# SAMD20_Xplained_Pro_Target_MCU.net
KiCad netlist of a schematic drawn in Altium Designer
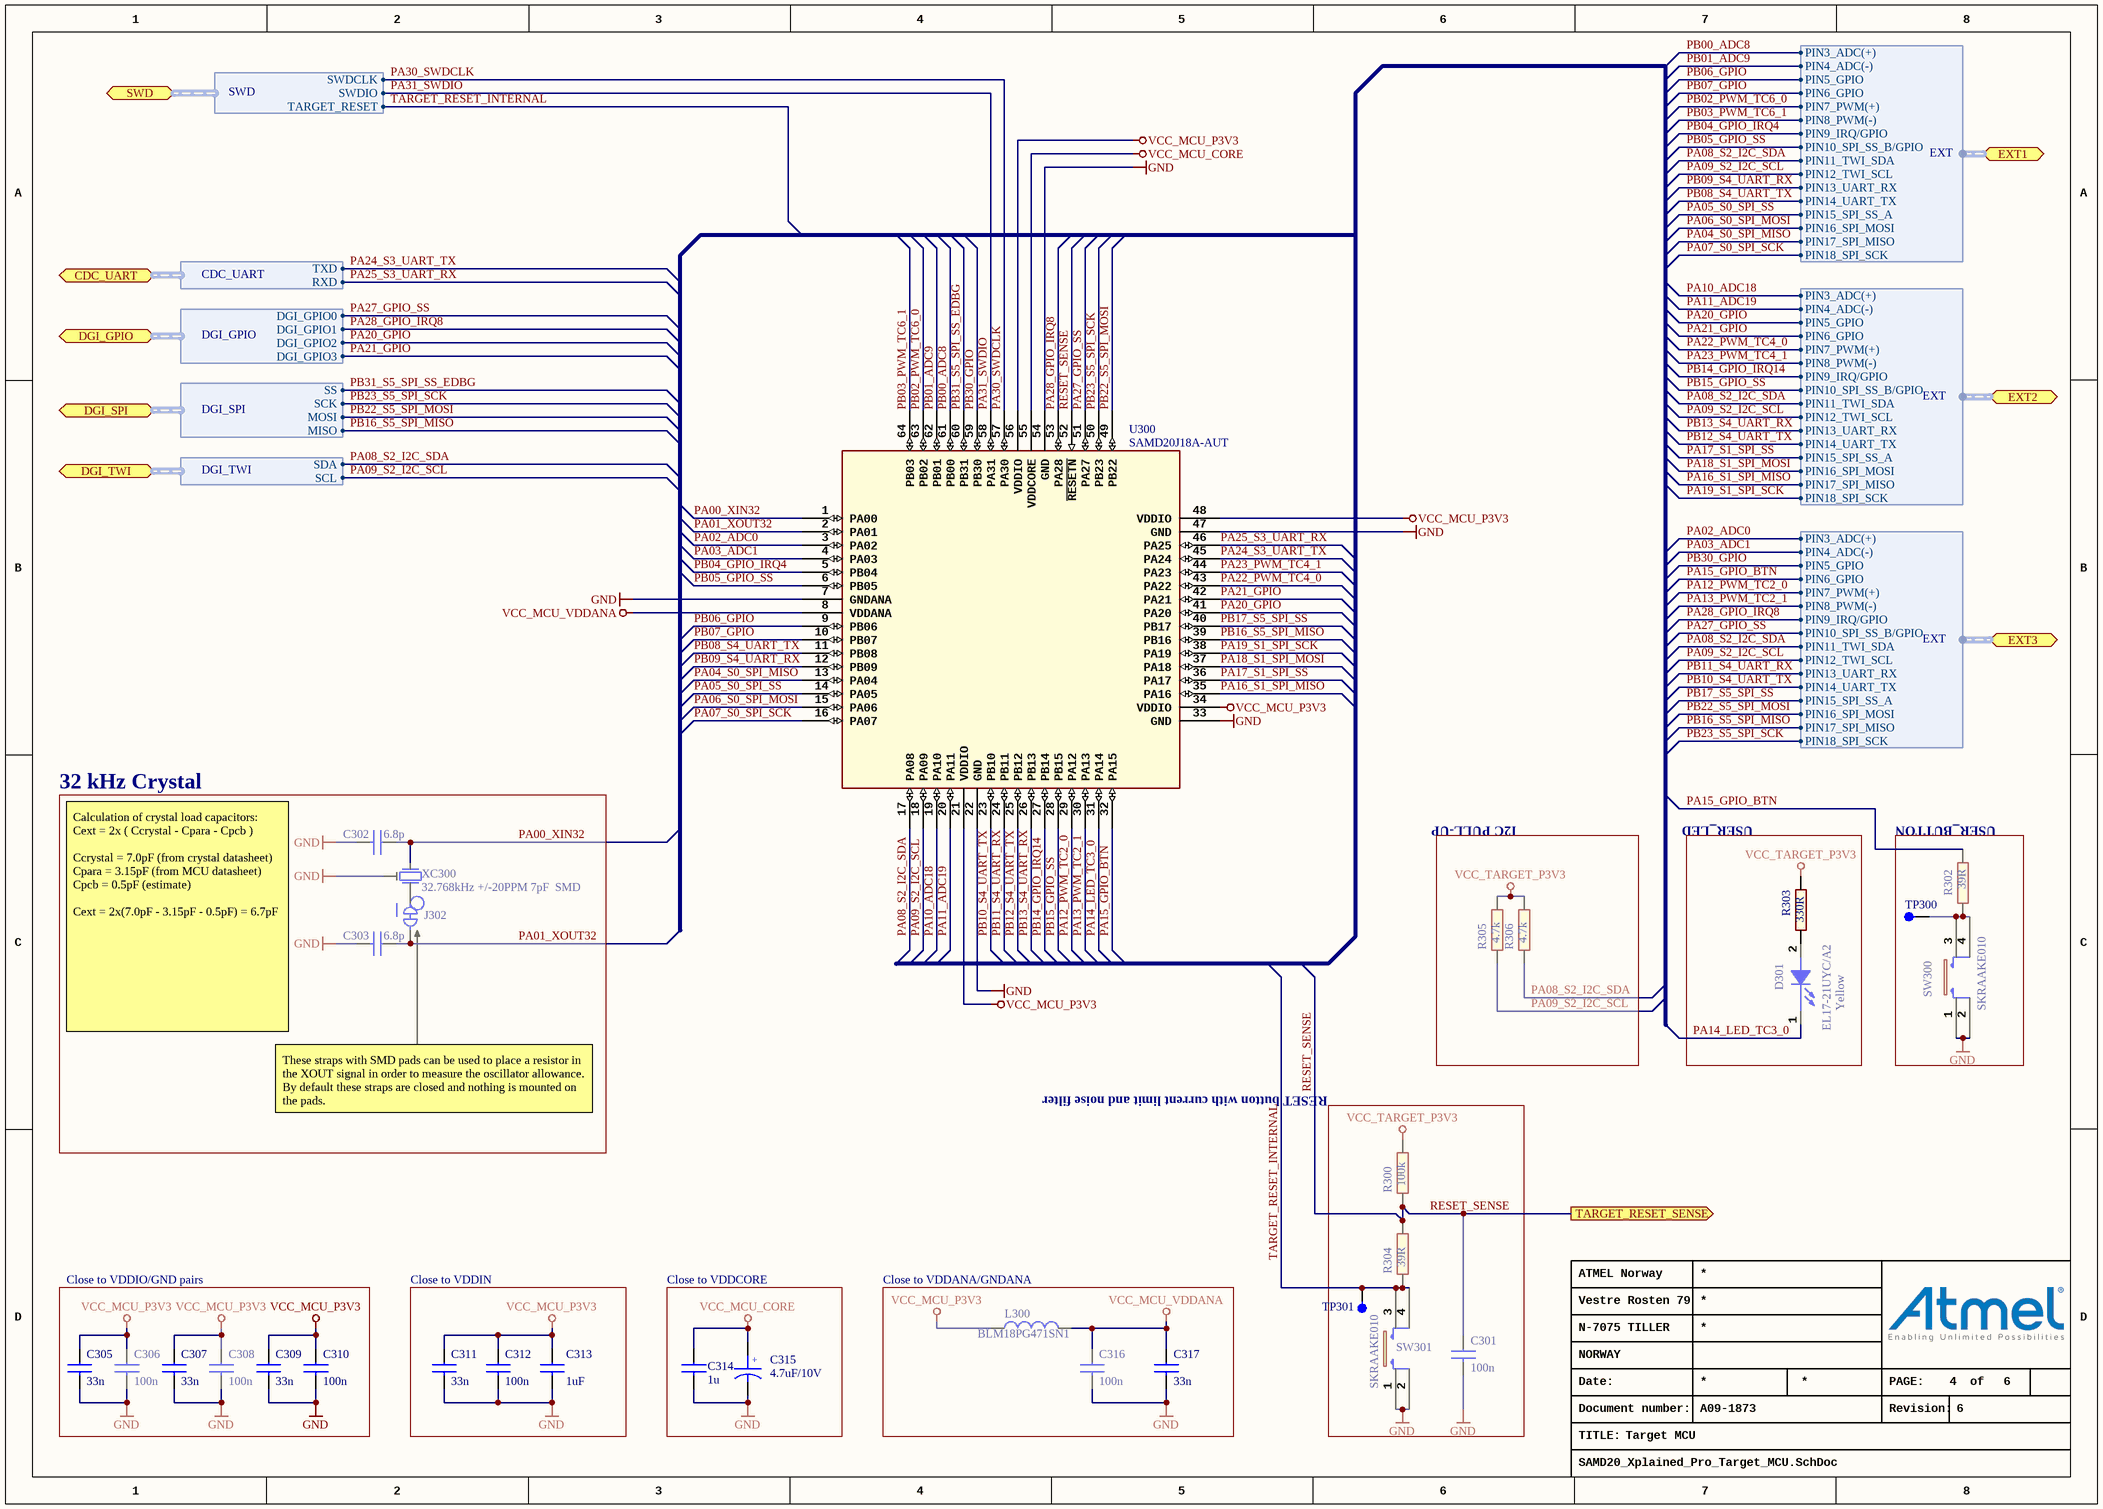
[diagram p0: SAMD20_Xplained_Pro_Target_MCU.SchDoc]

(export (version "E")
  (design (tool "Eeschema 10.0.6"))
  (components
    (comp (ref "C301")
      (value "100n")
      (footprint "AP1-00053")
      (description "Ceramic capacitor, SMD 0402, X7R, 16V, +/-10%")
      (fields (field (name "TOLERANCE") "16V, +/-10%") (field (name "MANUFACTURER") "Kemet"))
      (libsource (lib "AltiumDbLib") (part "CAP-NONPOL"))
    )
    (comp (ref "C302")
      (value "6.8p")
      (footprint "AP1-00001")
      (description "Ceramic capacitor, SMD 0402, NP0, 50V, +/-5%")
      (fields (field (name "TOLERANCE") "50V, +/-5%") (field (name "Comment") "CAP-NONPOL"))
      (libsource (lib "AltiumDbLib") (part "CAP-NONPOL"))
    )
    (comp (ref "C303")
      (value "6.8p")
      (footprint "AP1-00001")
      (description "Ceramic capacitor, SMD 0402, NP0, 50V, +/-5%")
      (fields (field (name "TOLERANCE") "50V, +/-5%") (field (name "Comment") "CAP-NONPOL"))
      (libsource (lib "AltiumDbLib") (part "CAP-NONPOL"))
    )
    (comp (ref "C305")
      (value "33n")
      (footprint "AP1-00001")
      (description "Ceramic capacitor, SMD 0402, X7R, 25V, ±10%")
      (fields (field (name "TOLERANCE") "±10%(K)") (field (name "MANUFACTURER") "Murata"))
      (libsource (lib "AltiumDbLib") (part "CAP-NONPOL"))
    )
    (comp (ref "C306")
      (value "100n")
      (footprint "AP1-00001")
      (description "Ceramic capacitor, SMD 0402, X7R, 16V, +/-10%")
      (fields (field (name "TOLERANCE") "16V, +/-10%") (field (name "MANUFACTURER") "Kemet"))
      (libsource (lib "AltiumDbLib") (part "CAP-NONPOL"))
    )
    (comp (ref "C307")
      (value "33n")
      (footprint "AP1-00001")
      (description "Ceramic capacitor, SMD 0402, X7R, 25V, ±10%")
      (fields (field (name "TOLERANCE") "±10%(K)") (field (name "MANUFACTURER") "Murata"))
      (libsource (lib "AltiumDbLib") (part "CAP-NONPOL"))
    )
    (comp (ref "C308")
      (value "100n")
      (footprint "AP1-00001")
      (description "Ceramic capacitor, SMD 0402, X7R, 16V, +/-10%")
      (fields (field (name "TOLERANCE") "16V, +/-10%") (field (name "MANUFACTURER") "Kemet"))
      (libsource (lib "AltiumDbLib") (part "CAP-NONPOL"))
    )
    (comp (ref "C309")
      (value "33n")
      (footprint "AP1-00001")
      (description "Ceramic capacitor, SMD 0402, X7R, 25V, ±10%")
      (fields (field (name "TOLERANCE") "±10%(K)") (field (name "MANUFACTURER") "Murata"))
      (libsource (lib "AltiumDbLib") (part "CAP-NONPOL"))
    )
    (comp (ref "C310")
      (value "100n")
      (footprint "AP1-00001")
      (description "Ceramic capacitor, SMD 0402, X7R, 16V, +/-10%")
      (fields (field (name "TOLERANCE") "16V, +/-10%") (field (name "MANUFACTURER") "Kemet"))
      (libsource (lib "AltiumDbLib") (part "CAP-NONPOL"))
    )
    (comp (ref "C311")
      (value "33n")
      (footprint "AP1-00001")
      (description "Ceramic capacitor, SMD 0402, X7R, 25V, ±10%")
      (fields (field (name "TOLERANCE") "±10%(K)") (field (name "MANUFACTURER") "Murata"))
      (libsource (lib "AltiumDbLib") (part "CAP-NONPOL"))
    )
    (comp (ref "C312")
      (value "100n")
      (footprint "AP1-00001")
      (description "Ceramic capacitor, SMD 0402, X7R, 16V, +/-10%")
      (fields (field (name "TOLERANCE") "16V, +/-10%") (field (name "MANUFACTURER") "Kemet"))
      (libsource (lib "AltiumDbLib") (part "CAP-NONPOL"))
    )
    (comp (ref "C313")
      (value "1uF")
      (footprint "AP1-00002")
      (description "Ceramic capacitor, SMD 0603, X5R, 25V, ±10%")
      (fields (field (name "TOLERANCE") "±10%") (field (name "MANUFACTURER") "Murata"))
      (libsource (lib "AltiumDbLib") (part "CAP-NONPOL"))
    )
    (comp (ref "C314")
      (value "1u")
      (footprint "AP1-00001")
      (description "Ceramic capacitor, SMD 0402, X5R, 6.3V, +/-10% (de26942)")
      (fields (field (name "TOLERANCE") "+/-10%") (field (name "MANUFACTURER") "Kemet"))
      (libsource (lib "AltiumDbLib") (part "CAP-NONPOL"))
    )
    (comp (ref "C315")
      (value "4.7uF/10V")
      (footprint "AP1-00036")
      (description "SMD tantalum capacitor, ESR = 5, 3216-18 (EIA) 1206, polarized")
      (fields (field (name "TOLERANCE") "+-10%") (field (name "MANUFACTURER") "Kemet"))
      (libsource (lib "AltiumDbLib") (part "CAP-POL"))
    )
    (comp (ref "C316")
      (value "100n")
      (footprint "AP1-00001")
      (description "Ceramic capacitor, SMD 0402, X7R, 16V, +/-10%")
      (fields (field (name "TOLERANCE") "16V, +/-10%") (field (name "MANUFACTURER") "Kemet"))
      (libsource (lib "AltiumDbLib") (part "CAP-NONPOL"))
    )
    (comp (ref "C317")
      (value "33n")
      (footprint "AP1-00001")
      (description "Ceramic capacitor, SMD 0402, X7R, 25V, ±10%")
      (fields (field (name "TOLERANCE") "±10%(K)") (field (name "MANUFACTURER") "Murata"))
      (libsource (lib "AltiumDbLib") (part "CAP-NONPOL"))
    )
    (comp (ref "D301")
      (value "Yellow")
      (footprint "AP4-00013")
      (description "LED, Yellow, Wave length=591nm, SMD 0805, ±70°")
      (fields
        (field (name "ALTIUM_VALUE") "EL17-21UYC/A2")
        (field (name "MANUFACTURER") "Everlight")
        (field (name "MPN") "17-21UYC/S530-A3/TR8")
      )
      (libsource (lib "AltiumDbLib") (part "LED_12"))
    )
    (comp (ref "J302")
      (value "~")
      (footprint "AP9-00044")
      (description "Default closed SMD strap, 0603 size")
      (libsource (lib "AltiumDbLib") (part "SMD-STRAP_CLOSED"))
    )
    (comp (ref "L300")
      (value "BLM18PG471SN1")
      (footprint "AP3-00005")
      (description "SMD RF inductor 0603. Z=470Ohm (@100MHz), Max R(dc)=0.65Ohm, Max current=1A")
      (fields (field (name "TOLERANCE") "±25%") (field (name "MANUFACTURER") "Murata"))
      (libsource (lib "AltiumDbLib") (part "INDUCTOR"))
    )
    (comp (ref "R300")
      (value "100k")
      (footprint "AP2-00000")
      (description "Thick film resistor, SMD 0402, 1/16W, 1%")
      (fields (field (name "TOLERANCE") "1 %") (field (name "Comment") "R2"))
      (libsource (lib "") (part "R2_1"))
    )
    (comp (ref "R302")
      (value "39R")
      (footprint "AP2-00011")
      (description "Thick film resistor, SMD 0402, 1/16W, 1%")
      (fields (field (name "TOLERANCE") "1 %") (field (name "Comment") "R2"))
      (libsource (lib "AltiumDbLib") (part "R2"))
    )
    (comp (ref "R303")
      (value "330R")
      (footprint "AP2-00000")
      (description "Thick film resistor, SMD 0402, 1/16W, 1%")
      (fields (field (name "TOLERANCE") "1 %") (field (name "Comment") "R2"))
      (libsource (lib "") (part "R2_1"))
    )
    (comp (ref "R304")
      (value "39R")
      (footprint "AP2-00011")
      (description "Thick film resistor, SMD 0402, 1/16W, 1%")
      (fields (field (name "TOLERANCE") "1 %") (field (name "Comment") "R2"))
      (libsource (lib "AltiumDbLib") (part "R2"))
    )
    (comp (ref "R305")
      (value "4.7k")
      (footprint "AP2-00000")
      (description "Thick film resistor, SMD 0402, 1/16W, 1%")
      (fields (field (name "TOLERANCE") "1 %") (field (name "Comment") "R2"))
      (libsource (lib "") (part "R2_1"))
    )
    (comp (ref "R306")
      (value "4.7k")
      (footprint "AP2-00000")
      (description "Thick film resistor, SMD 0402, 1/16W, 1%")
      (fields (field (name "TOLERANCE") "1 %") (field (name "Comment") "R2"))
      (libsource (lib "") (part "R2_1"))
    )
    (comp (ref "SW300")
      (value "SKRAAKE010")
      (footprint "AP8-00137")
      (description "6.2x6.2 mm SMD tact switch, same as A08-0091 but less force is needed")
      (fields
        (field (name "MANUFACTURER") "ALPS")
        (field (name "Comment") "Can be ordered in low volumes from Mouser")
      )
      (libsource (lib "AltiumDbLib") (part "PUSHBUTTON1"))
    )
    (comp (ref "SW301")
      (value "SKRAAKE010")
      (footprint "AP8-00137")
      (description "6.2x6.2 mm SMD tact switch, same as A08-0091 but less force is needed")
      (fields
        (field (name "MANUFACTURER") "ALPS")
        (field (name "Comment") "Can be ordered in low volumes from Mouser")
      )
      (libsource (lib "AltiumDbLib") (part "PUSHBUTTON1"))
    )
    (comp (ref "TP300")
      (value "TESTPOINT")
      (footprint "AP8-00010")
      (description "Single SMD testpad")
      (libsource (lib "AltiumDbLib") (part "TESTPOINT"))
    )
    (comp (ref "TP301")
      (value "TESTPOINT")
      (footprint "AP8-00010")
      (description "Single SMD testpad")
      (libsource (lib "AltiumDbLib") (part "TESTPOINT"))
    )
    (comp (ref "U300")
      (value "SAMD20J18A-AUT")
      (footprint "AP6-00173")
      (description "Atmel 32-bit RISC MCU")
      (fields (field (name "MANUFACTURER") "ATMEL") (field (name "Comment") "TQFP64"))
      (libsource (lib "AltiumDbLib") (part "SAMD20J"))
    )
    (comp (ref "XC300")
      (value "32.768kHz +/-20PPM 7pF  SMD")
      (footprint "AP7-00044")
      (description "32k768 crystal, +-20ppm, CL=7pF, max ESR 60kOhm, SMD")
      (fields (field (name "TOLERANCE") "+/- 20 PPM") (field (name "MANUFACTURER") "Micro Crystal"))
      (libsource (lib "AltiumDbLib") (part "CRYSTAL_2P_metal"))
    )
  )
  (nets
    (net (code "7") (name "/PA00_XIN32") (class "Default")
      (node (ref "C302") (pin "1") (pinfunction "1_1") (pintype "passive"))
      (node (ref "U300") (pin "1") (pinfunction "PA00_1") (pintype "bidirectional"))
      (node (ref "XC300") (pin "2") (pinfunction "2_2") (pintype "passive"))
    )
    (net (code "8") (name "/PA01_XOUT32") (class "Default")
      (node (ref "C303") (pin "1") (pinfunction "1_1") (pintype "passive"))
      (node (ref "J302") (pin "2") (pinfunction "2_2") (pintype "passive"))
      (node (ref "U300") (pin "2") (pinfunction "PA01_2") (pintype "bidirectional"))
    )
    (net (code "9") (name "/PA02_ADC0") (class "Default")
      (node (ref "U300") (pin "3") (pinfunction "PA02_3") (pintype "bidirectional"))
    )
    (net (code "10") (name "/PA03_ADC1") (class "Default")
      (node (ref "U300") (pin "4") (pinfunction "PA03_4") (pintype "bidirectional"))
    )
    (net (code "11") (name "/PA04_S0_SPI_MISO") (class "Default")
      (node (ref "U300") (pin "13") (pinfunction "PA04_13") (pintype "bidirectional"))
    )
    (net (code "12") (name "/PA05_S0_SPI_SS") (class "Default")
      (node (ref "U300") (pin "14") (pinfunction "PA05_14") (pintype "bidirectional"))
    )
    (net (code "13") (name "/PA06_S0_SPI_MOSI") (class "Default")
      (node (ref "U300") (pin "15") (pinfunction "PA06_15") (pintype "bidirectional"))
    )
    (net (code "14") (name "/PA07_S0_SPI_SCK") (class "Default")
      (node (ref "U300") (pin "16") (pinfunction "PA07_16") (pintype "bidirectional"))
    )
    (net (code "15") (name "/PA08_S2_I2C_SDA") (class "Default")
      (node (ref "R306") (pin "1") (pinfunction "1_1") (pintype "passive"))
      (node (ref "U300") (pin "17") (pinfunction "PA08_17") (pintype "bidirectional"))
    )
    (net (code "16") (name "/PA09_S2_I2C_SCL") (class "Default")
      (node (ref "R305") (pin "1") (pinfunction "1_1") (pintype "passive"))
      (node (ref "U300") (pin "18") (pinfunction "PA09_18") (pintype "bidirectional"))
    )
    (net (code "17") (name "/PA10_ADC18") (class "Default")
      (node (ref "U300") (pin "19") (pinfunction "PA10_19") (pintype "bidirectional"))
    )
    (net (code "18") (name "/PA11_ADC19") (class "Default")
      (node (ref "U300") (pin "20") (pinfunction "PA11_20") (pintype "bidirectional"))
    )
    (net (code "19") (name "/PA12_PWM_TC2_0") (class "Default")
      (node (ref "U300") (pin "29") (pinfunction "PA12_29") (pintype "bidirectional"))
    )
    (net (code "20") (name "/PA13_PWM_TC2_1") (class "Default")
      (node (ref "U300") (pin "30") (pinfunction "PA13_30") (pintype "bidirectional"))
    )
    (net (code "21") (name "/PA14_LED_TC3_0") (class "Default")
      (node (ref "D301") (pin "1") (pinfunction "CATHODE_1") (pintype "passive"))
      (node (ref "U300") (pin "31") (pinfunction "PA14_31") (pintype "bidirectional"))
    )
    (net (code "22") (name "/PA15_GPIO_BTN") (class "Default")
      (node (ref "R302") (pin "2") (pinfunction "2_2") (pintype "passive"))
      (node (ref "U300") (pin "32") (pinfunction "PA15_32") (pintype "bidirectional"))
    )
    (net (code "23") (name "/PA16_S1_SPI_MISO") (class "Default")
      (node (ref "U300") (pin "35") (pinfunction "PA16_35") (pintype "bidirectional"))
    )
    (net (code "24") (name "/PA17_S1_SPI_SS") (class "Default")
      (node (ref "U300") (pin "36") (pinfunction "PA17_36") (pintype "bidirectional"))
    )
    (net (code "25") (name "/PA18_S1_SPI_MOSI") (class "Default")
      (node (ref "U300") (pin "37") (pinfunction "PA18_37") (pintype "bidirectional"))
    )
    (net (code "26") (name "/PA19_S1_SPI_SCK") (class "Default")
      (node (ref "U300") (pin "38") (pinfunction "PA19_38") (pintype "bidirectional"))
    )
    (net (code "27") (name "/PA20_GPIO") (class "Default")
      (node (ref "U300") (pin "41") (pinfunction "PA20_41") (pintype "bidirectional"))
    )
    (net (code "28") (name "/PA21_GPIO") (class "Default")
      (node (ref "U300") (pin "42") (pinfunction "PA21_42") (pintype "bidirectional"))
    )
    (net (code "29") (name "/PA22_PWM_TC4_0") (class "Default")
      (node (ref "U300") (pin "43") (pinfunction "PA22_43") (pintype "bidirectional"))
    )
    (net (code "30") (name "/PA23_PWM_TC4_1") (class "Default")
      (node (ref "U300") (pin "44") (pinfunction "PA23_44") (pintype "bidirectional"))
    )
    (net (code "31") (name "/PA24_S3_UART_TX") (class "Default")
      (node (ref "U300") (pin "45") (pinfunction "PA24_45") (pintype "bidirectional"))
    )
    (net (code "32") (name "/PA25_S3_UART_RX") (class "Default")
      (node (ref "U300") (pin "46") (pinfunction "PA25_46") (pintype "bidirectional"))
    )
    (net (code "33") (name "/PA27_GPIO_SS") (class "Default")
      (node (ref "U300") (pin "51") (pinfunction "PA27_51") (pintype "bidirectional"))
    )
    (net (code "34") (name "/PA28_GPIO_IRQ8") (class "Default")
      (node (ref "U300") (pin "53") (pinfunction "PA28_53") (pintype "bidirectional"))
    )
    (net (code "35") (name "/PA30_SWDCLK") (class "Default")
      (node (ref "U300") (pin "57") (pinfunction "PA30_57") (pintype "bidirectional"))
    )
    (net (code "36") (name "/PA31_SWDIO") (class "Default")
      (node (ref "U300") (pin "58") (pinfunction "PA31_58") (pintype "bidirectional"))
    )
    (net (code "37") (name "/PB00_ADC8") (class "Default")
      (node (ref "U300") (pin "61") (pinfunction "PB00_61") (pintype "bidirectional"))
    )
    (net (code "38") (name "/PB01_ADC9") (class "Default")
      (node (ref "U300") (pin "62") (pinfunction "PB01_62") (pintype "bidirectional"))
    )
    (net (code "39") (name "/PB02_PWM_TC6_0") (class "Default")
      (node (ref "U300") (pin "63") (pinfunction "PB02_63") (pintype "bidirectional"))
    )
    (net (code "40") (name "/PB03_PWM_TC6_1") (class "Default")
      (node (ref "U300") (pin "64") (pinfunction "PB03_64") (pintype "bidirectional"))
    )
    (net (code "41") (name "/PB04_GPIO_IRQ4") (class "Default")
      (node (ref "U300") (pin "5") (pinfunction "PB04_5") (pintype "bidirectional"))
    )
    (net (code "42") (name "/PB05_GPIO_SS") (class "Default")
      (node (ref "U300") (pin "6") (pinfunction "PB05_6") (pintype "bidirectional"))
    )
    (net (code "43") (name "/PB06_GPIO") (class "Default")
      (node (ref "U300") (pin "9") (pinfunction "PB06_9") (pintype "bidirectional"))
    )
    (net (code "44") (name "/PB07_GPIO") (class "Default")
      (node (ref "U300") (pin "10") (pinfunction "PB07_10") (pintype "bidirectional"))
    )
    (net (code "45") (name "/PB08_S4_UART_TX") (class "Default")
      (node (ref "U300") (pin "11") (pinfunction "PB08_11") (pintype "bidirectional"))
    )
    (net (code "46") (name "/PB09_S4_UART_RX") (class "Default")
      (node (ref "U300") (pin "12") (pinfunction "PB09_12") (pintype "bidirectional"))
    )
    (net (code "47") (name "/PB10_S4_UART_TX") (class "Default")
      (node (ref "U300") (pin "23") (pinfunction "PB10_23") (pintype "bidirectional"))
    )
    (net (code "48") (name "/PB11_S4_UART_RX") (class "Default")
      (node (ref "U300") (pin "24") (pinfunction "PB11_24") (pintype "bidirectional"))
    )
    (net (code "49") (name "/PB12_S4_UART_TX") (class "Default")
      (node (ref "U300") (pin "25") (pinfunction "PB12_25") (pintype "bidirectional"))
    )
    (net (code "50") (name "/PB13_S4_UART_RX") (class "Default")
      (node (ref "U300") (pin "26") (pinfunction "PB13_26") (pintype "bidirectional"))
    )
    (net (code "51") (name "/PB14_GPIO_IRQ14") (class "Default")
      (node (ref "U300") (pin "27") (pinfunction "PB14_27") (pintype "bidirectional"))
    )
    (net (code "52") (name "/PB15_GPIO_SS") (class "Default")
      (node (ref "U300") (pin "28") (pinfunction "PB15_28") (pintype "bidirectional"))
    )
    (net (code "53") (name "/PB16_S5_SPI_MISO") (class "Default")
      (node (ref "U300") (pin "39") (pinfunction "PB16_39") (pintype "bidirectional"))
    )
    (net (code "54") (name "/PB17_S5_SPI_SS") (class "Default")
      (node (ref "U300") (pin "40") (pinfunction "PB17_40") (pintype "bidirectional"))
    )
    (net (code "55") (name "/PB22_S5_SPI_MOSI") (class "Default")
      (node (ref "U300") (pin "49") (pinfunction "PB22_49") (pintype "bidirectional"))
    )
    (net (code "56") (name "/PB23_S5_SPI_SCK") (class "Default")
      (node (ref "U300") (pin "50") (pinfunction "PB23_50") (pintype "bidirectional"))
    )
    (net (code "57") (name "/PB30_GPIO") (class "Default")
      (node (ref "U300") (pin "59") (pinfunction "PB30_59") (pintype "bidirectional"))
    )
    (net (code "58") (name "/PB31_S5_SPI_SS_EDBG") (class "Default")
      (node (ref "U300") (pin "60") (pinfunction "PB31_60") (pintype "bidirectional"))
    )
    (net (code "59") (name "/RESET_SENSE") (class "Default")
      (node (ref "C301") (pin "1") (pinfunction "1_1") (pintype "passive"))
      (node (ref "R300") (pin "1") (pinfunction "1_1") (pintype "passive"))
      (node (ref "R304") (pin "2") (pinfunction "2_2") (pintype "passive"))
      (node (ref "U300") (pin "52") (pinfunction "~{RESETN}_52") (pintype "input"))
    )
    (net (code "60") (name "/TARGET_RESET_INTERNAL") (class "Default")
      (node (ref "R304") (pin "1") (pinfunction "1_1") (pintype "passive"))
      (node (ref "SW301") (pin "3") (pinfunction "3_3") (pintype "passive"))
      (node (ref "SW301") (pin "4") (pinfunction "4_4") (pintype "passive"))
      (node (ref "TP301") (pin "1") (pinfunction "1_1") (pintype "passive"))
    )
    (net (code "67") (name "GND") (class "Default")
      (node (ref "C301") (pin "2") (pinfunction "2_2") (pintype "passive"))
      (node (ref "C302") (pin "2") (pinfunction "2_2") (pintype "passive"))
      (node (ref "C303") (pin "2") (pinfunction "2_2") (pintype "passive"))
      (node (ref "C305") (pin "2") (pinfunction "2_2") (pintype "passive"))
      (node (ref "C306") (pin "2") (pinfunction "2_2") (pintype "passive"))
      (node (ref "C307") (pin "2") (pinfunction "2_2") (pintype "passive"))
      (node (ref "C308") (pin "2") (pinfunction "2_2") (pintype "passive"))
      (node (ref "C309") (pin "2") (pinfunction "2_2") (pintype "passive"))
      (node (ref "C310") (pin "2") (pinfunction "2_2") (pintype "passive"))
      (node (ref "C311") (pin "2") (pinfunction "2_2") (pintype "passive"))
      (node (ref "C312") (pin "2") (pinfunction "2_2") (pintype "passive"))
      (node (ref "C313") (pin "2") (pinfunction "2_2") (pintype "passive"))
      (node (ref "C314") (pin "2") (pinfunction "2_2") (pintype "passive"))
      (node (ref "C315") (pin "2") (pinfunction "2_2") (pintype "passive"))
      (node (ref "C316") (pin "2") (pinfunction "2_2") (pintype "passive"))
      (node (ref "C317") (pin "2") (pinfunction "2_2") (pintype "passive"))
      (node (ref "SW300") (pin "1") (pinfunction "1_1") (pintype "passive"))
      (node (ref "SW300") (pin "2") (pinfunction "2_2") (pintype "passive"))
      (node (ref "SW301") (pin "1") (pinfunction "1_1") (pintype "passive"))
      (node (ref "SW301") (pin "2") (pinfunction "2_2") (pintype "passive"))
      (node (ref "U300") (pin "22") (pinfunction "GND_22") (pintype "power_in"))
      (node (ref "U300") (pin "33") (pinfunction "GND_33") (pintype "power_in"))
      (node (ref "U300") (pin "47") (pinfunction "GND_47") (pintype "power_in"))
      (node (ref "U300") (pin "54") (pinfunction "GND_54") (pintype "power_in"))
      (node (ref "U300") (pin "7") (pinfunction "GNDANA_7") (pintype "power_in"))
      (node (ref "XC300") (pin "3") (pinfunction "3_3") (pintype "passive"))
    )
    (net (code "68") (name "Net-(D301-ANODE)") (class "Default")
      (node (ref "D301") (pin "2") (pinfunction "ANODE_2") (pintype "passive"))
      (node (ref "R303") (pin "1") (pinfunction "1_1") (pintype "passive"))
    )
    (net (code "69") (name "Net-(J302-Pad1)") (class "Default")
      (node (ref "J302") (pin "1") (pinfunction "1_1") (pintype "passive"))
      (node (ref "XC300") (pin "1") (pinfunction "1_1") (pintype "passive"))
    )
    (net (code "70") (name "Net-(R302-Pad1)") (class "Default")
      (node (ref "R302") (pin "1") (pinfunction "1_1") (pintype "passive"))
      (node (ref "SW300") (pin "3") (pinfunction "3_3") (pintype "passive"))
      (node (ref "SW300") (pin "4") (pinfunction "4_4") (pintype "passive"))
      (node (ref "TP300") (pin "1") (pinfunction "1_1") (pintype "passive"))
    )
    (net (code "71") (name "VCC_MCU_CORE") (class "Default")
      (node (ref "C314") (pin "1") (pinfunction "1_1") (pintype "passive"))
      (node (ref "C315") (pin "1") (pinfunction "1_1") (pintype "passive"))
      (node (ref "U300") (pin "55") (pinfunction "VDDCORE_55") (pintype "power_in"))
    )
    (net (code "72") (name "VCC_MCU_P3V3") (class "Default")
      (node (ref "C305") (pin "1") (pinfunction "1_1") (pintype "passive"))
      (node (ref "C306") (pin "1") (pinfunction "1_1") (pintype "passive"))
      (node (ref "C307") (pin "1") (pinfunction "1_1") (pintype "passive"))
      (node (ref "C308") (pin "1") (pinfunction "1_1") (pintype "passive"))
      (node (ref "C309") (pin "1") (pinfunction "1_1") (pintype "passive"))
      (node (ref "C310") (pin "1") (pinfunction "1_1") (pintype "passive"))
      (node (ref "C311") (pin "1") (pinfunction "1_1") (pintype "passive"))
      (node (ref "C312") (pin "1") (pinfunction "1_1") (pintype "passive"))
      (node (ref "C313") (pin "1") (pinfunction "1_1") (pintype "passive"))
      (node (ref "L300") (pin "1") (pinfunction "1_1") (pintype "passive"))
      (node (ref "U300") (pin "21") (pinfunction "VDDIO_21") (pintype "power_in"))
      (node (ref "U300") (pin "34") (pinfunction "VDDIO_34") (pintype "power_in"))
      (node (ref "U300") (pin "48") (pinfunction "VDDIO_48") (pintype "power_in"))
      (node (ref "U300") (pin "56") (pinfunction "VDDIO_56") (pintype "power_in"))
    )
    (net (code "73") (name "VCC_MCU_VDDANA") (class "Default")
      (node (ref "C316") (pin "1") (pinfunction "1_1") (pintype "passive"))
      (node (ref "C317") (pin "1") (pinfunction "1_1") (pintype "passive"))
      (node (ref "L300") (pin "2") (pinfunction "2_2") (pintype "passive"))
      (node (ref "U300") (pin "8") (pinfunction "VDDANA_8") (pintype "power_in"))
    )
    (net (code "74") (name "VCC_TARGET_P3V3") (class "Default")
      (node (ref "R300") (pin "2") (pinfunction "2_2") (pintype "passive"))
      (node (ref "R303") (pin "2") (pinfunction "2_2") (pintype "passive"))
      (node (ref "R305") (pin "2") (pinfunction "2_2") (pintype "passive"))
      (node (ref "R306") (pin "2") (pinfunction "2_2") (pintype "passive"))
    )
  )
)
